# SSTuino_Evo.net
KiCad netlist of a schematic drawn in EAGLE
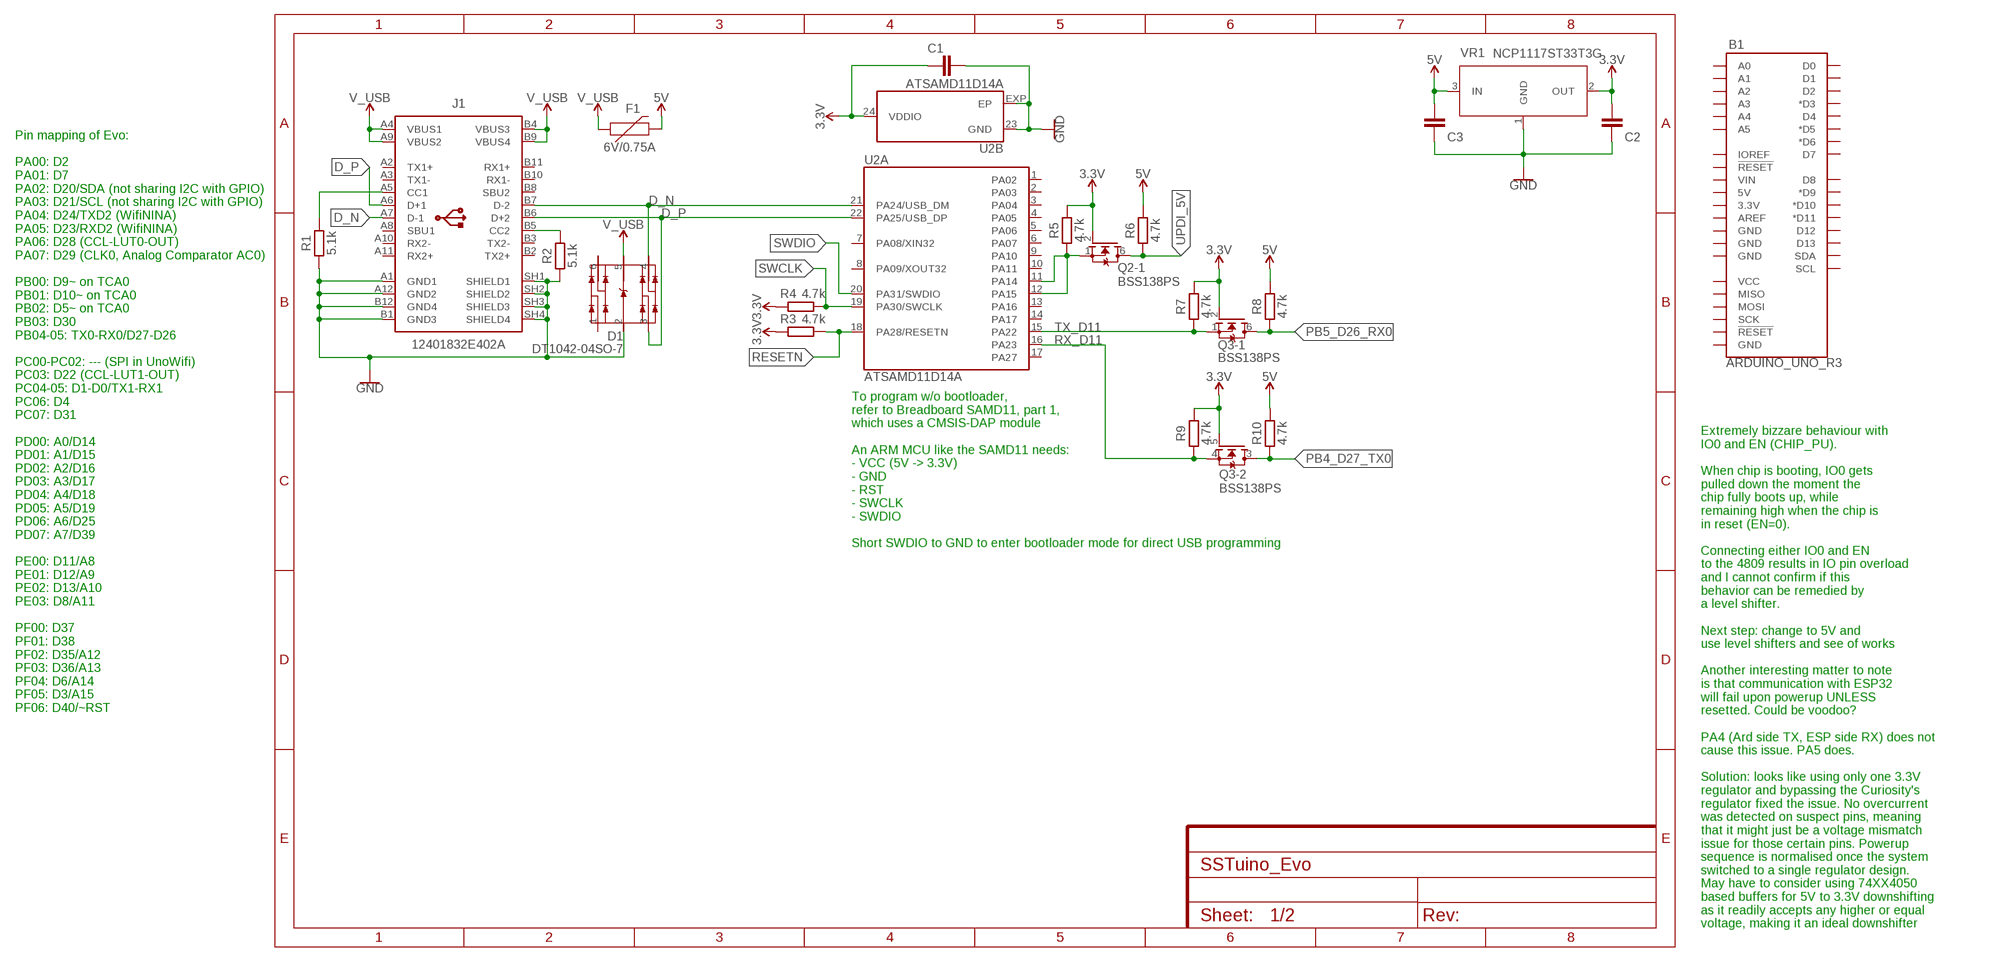
[diagram p0: schematic, sheet 1]
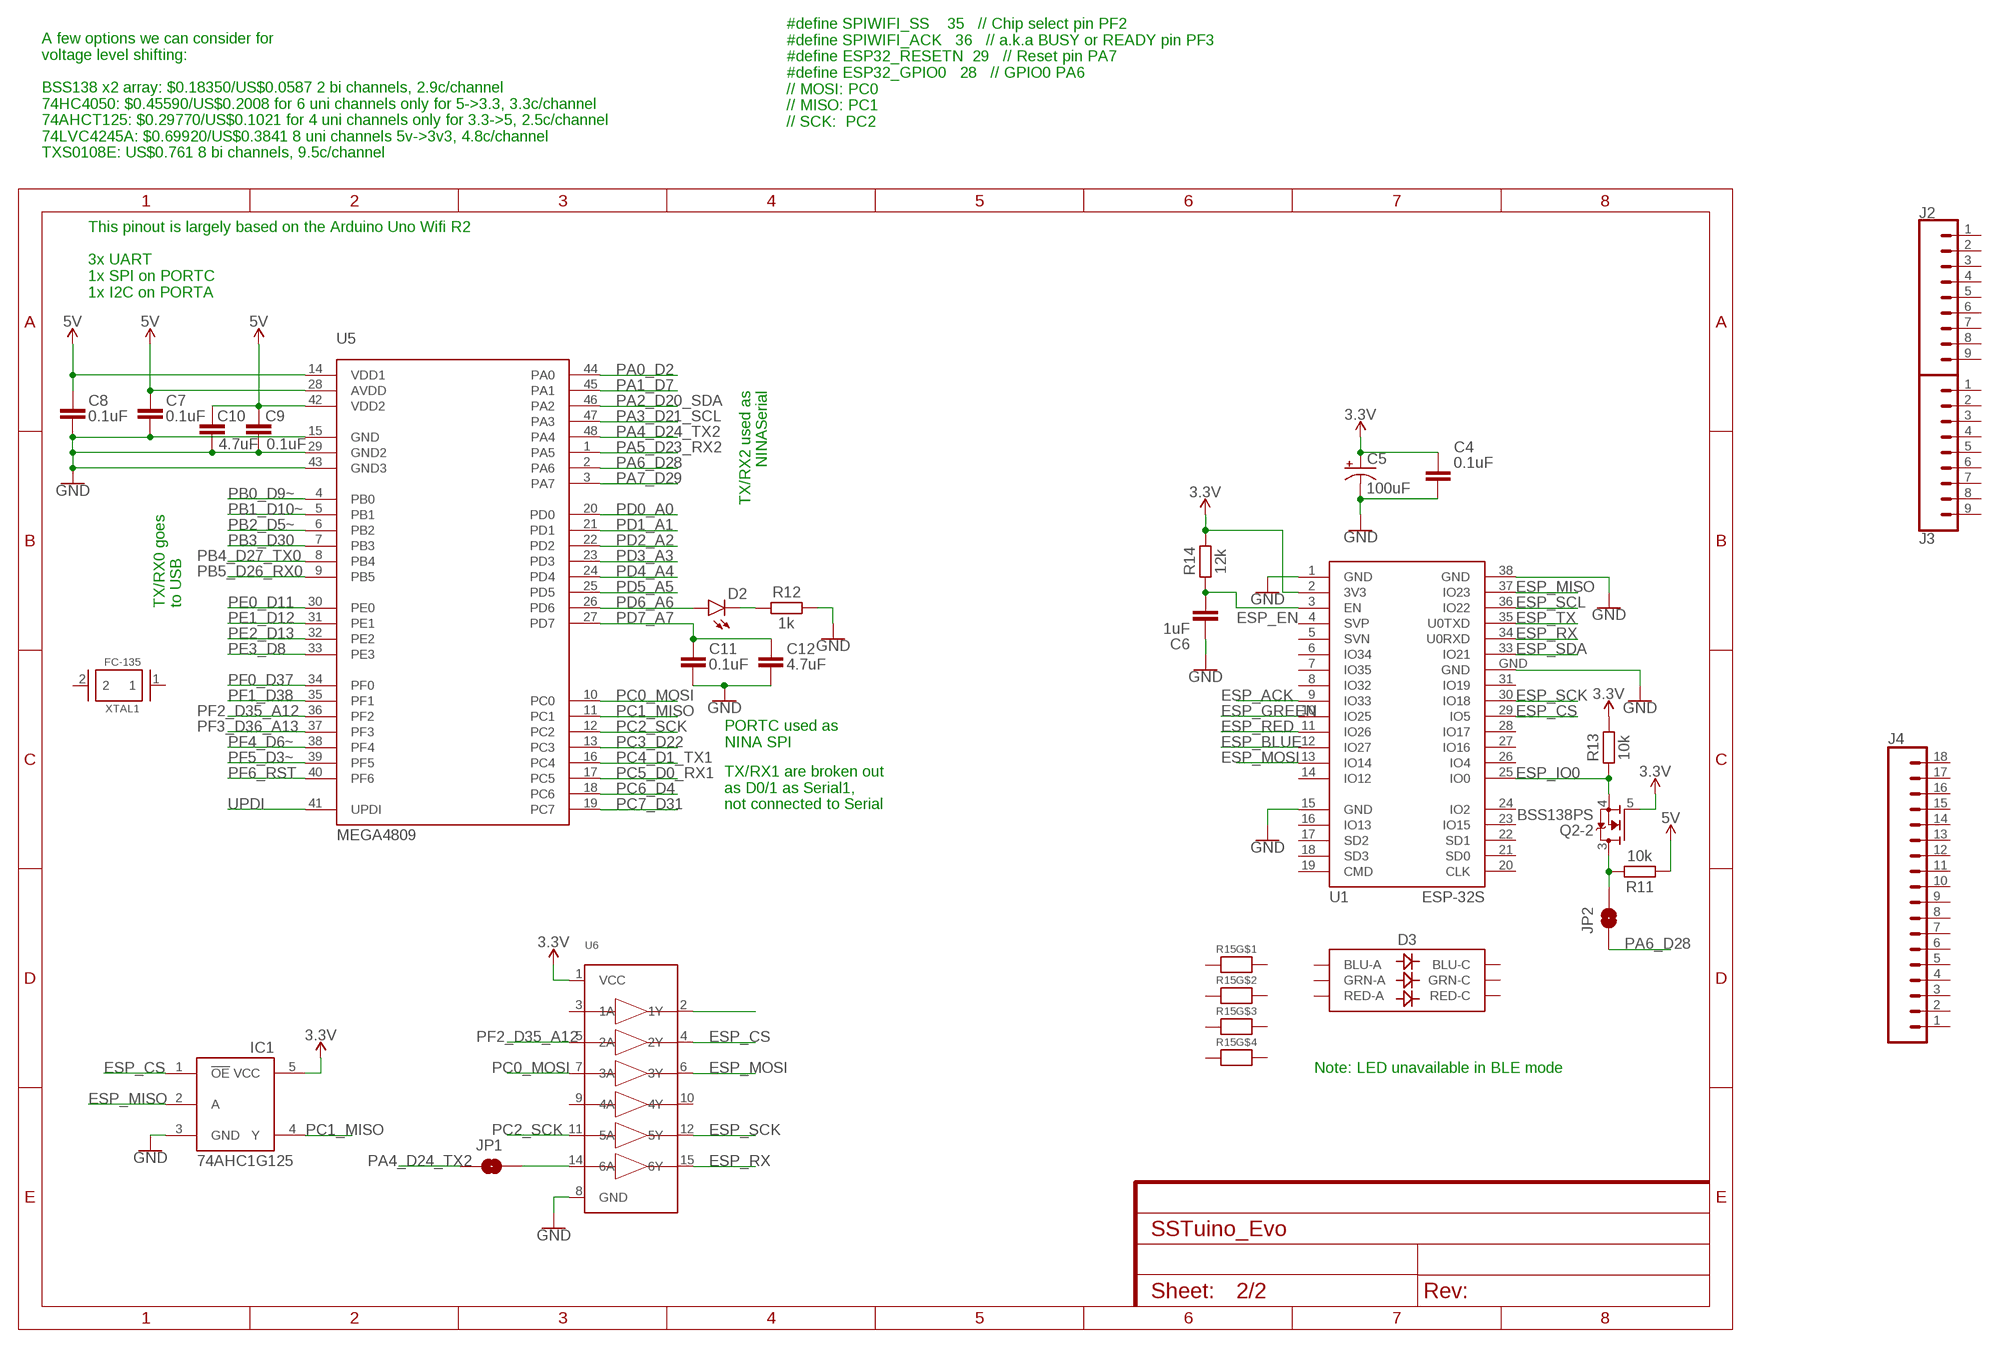
[diagram p1: schematic, sheet 2]

(export (version "E")
  (design (tool "Eeschema 10.0.6"))
  (components
    (comp (ref "C4")
      (value "0.1uF")
      (footprint "eagle-import:CAPC1005X60")
      (libsource (lib "eagle-import") (part "CCHIP-0402(1005-METRIC)_"))
    )
    (comp (ref "C5")
      (value "100uF")
      (footprint "eagle-import:CAPMP3216X180N")
      (libsource (lib "eagle-import") (part "C-POL-USTANTALUM-1206(3216-METRIC)_"))
    )
    (comp (ref "C6")
      (value "1uF")
      (footprint "eagle-import:CAPC1005X60")
      (libsource (lib "eagle-import") (part "CCHIP-0402(1005-METRIC)_"))
    )
    (comp (ref "C7")
      (value "0.1uF")
      (footprint "eagle-import:CAPC1005X60")
      (libsource (lib "eagle-import") (part "CCHIP-0402(1005-METRIC)_"))
    )
    (comp (ref "C8")
      (value "0.1uF")
      (footprint "eagle-import:CAPC1005X60")
      (libsource (lib "eagle-import") (part "CCHIP-0402(1005-METRIC)_"))
    )
    (comp (ref "C9")
      (value "0.1uF")
      (footprint "eagle-import:CAPC1005X60")
      (libsource (lib "eagle-import") (part "CCHIP-0402(1005-METRIC)_"))
    )
    (comp (ref "C10")
      (value "4.7uF")
      (footprint "eagle-import:CAPC1005X60")
      (libsource (lib "eagle-import") (part "CCHIP-0402(1005-METRIC)_"))
    )
    (comp (ref "C11")
      (value "0.1uF")
      (footprint "eagle-import:CAPC1005X60")
      (libsource (lib "eagle-import") (part "CCHIP-0402(1005-METRIC)_"))
    )
    (comp (ref "C12")
      (value "4.7uF")
      (footprint "eagle-import:CAPC1005X60")
      (libsource (lib "eagle-import") (part "CCHIP-0402(1005-METRIC)_"))
    )
    (comp (ref "D2")
      (value "LED0603")
      (footprint "eagle-import:LED-0603")
      (libsource (lib "eagle-import") (part "LED0603"))
    )
    (comp (ref "D3")
      (value "LED-RGBNO_IC")
      (footprint "eagle-import:LED-TRICOLOR-5050")
      (libsource (lib "eagle-import") (part "LED-RGBNO_IC"))
    )
    (comp (ref "IC1")
      (value "74AHC1G125")
      (footprint "eagle-import:SOT23-5L")
      (libsource (lib "eagle-import") (part "74AHC1G125"))
    )
    (comp (ref "J2")
      (value "CONN_09NO_SILK")
      (footprint "eagle-import:1X09_NO_SILK")
      (libsource (lib "eagle-import") (part "CONN_09NO_SILK"))
    )
    (comp (ref "J3")
      (value "CONN_09NO_SILK")
      (footprint "eagle-import:1X09_NO_SILK")
      (libsource (lib "eagle-import") (part "CONN_09NO_SILK"))
    )
    (comp (ref "J4")
      (value "CONN_18")
      (footprint "eagle-import:1X18")
      (libsource (lib "eagle-import") (part "CONN_18"))
    )
    (comp (ref "JP1")
      (value "JUMPER-SMT_2_NO_SILK")
      (footprint "eagle-import:SMT-JUMPER_2_NO_SILK")
      (libsource (lib "eagle-import") (part "JUMPER-SMT_2_NO_SILK"))
    )
    (comp (ref "JP2")
      (value "JUMPER-SMT_2_NO_SILK")
      (footprint "eagle-import:SMT-JUMPER_2_NO_SILK")
      (libsource (lib "eagle-import") (part "JUMPER-SMT_2_NO_SILK"))
    )
    (comp (ref "Q2")
      (value "BSS138PS")
      (footprint "eagle-import:ARDUINO-TRANSISTORS_SOT363")
      (fields (field (name "MANUFACTURER") "NXP"))
      (libsource (lib "eagle-import") (part "BSS138PS"))
    )
    (comp (ref "R11")
      (value "10k")
      (footprint "eagle-import:RESC1005X40")
      (libsource (lib "eagle-import") (part "RCHIP-0402(1005-METRIC)_"))
    )
    (comp (ref "R12")
      (value "1k")
      (footprint "eagle-import:RESC1005X40")
      (libsource (lib "eagle-import") (part "RCHIP-0402(1005-METRIC)_"))
    )
    (comp (ref "R13")
      (value "10k")
      (footprint "eagle-import:RESC1005X40")
      (libsource (lib "eagle-import") (part "RCHIP-0402(1005-METRIC)_"))
    )
    (comp (ref "R14")
      (value "12k")
      (footprint "eagle-import:RESC1005X40")
      (libsource (lib "eagle-import") (part "RCHIP-0402(1005-METRIC)_"))
    )
    (comp (ref "R15")
      (value "RESISTOR_4PACK")
      (footprint "eagle-import:RESPACK_4X0603")
      (libsource (lib "eagle-import") (part "RESISTOR_4PACK"))
    )
    (comp (ref "U1")
      (value "ESP-32S")
      (footprint "eagle-import:ESP-32S")
      (libsource (lib "eagle-import") (part "ESP-32S"))
    )
    (comp (ref "U5")
      (value "MEGA4809")
      (footprint "eagle-import:TQFP48")
      (libsource (lib "eagle-import") (part "MEGA4809"))
    )
    (comp (ref "U6")
      (value "74HC4050DTSSOP")
      (footprint "eagle-import:TSSOP16")
      (libsource (lib "eagle-import") (part "74HC4050DTSSOP"))
    )
    (comp (ref "XTAL1")
      (value "FC-135")
      (footprint "eagle-import:XTAL330X1051X90N")
      (fields (field (name "MANUFACTURER") "Seiko Epson Corporation"))
      (libsource (lib "eagle-import") (part "FC-135"))
    )
    (comp (ref "B1")
      (value "ARDUINO_UNO_R3")
      (footprint "eagle-import:ARDUINO_R3")
      (libsource (lib "eagle-import") (part "ARDUINO_UNO_R3"))
    )
    (comp (ref "C1")
      (value "100n")
      (footprint "eagle-import:CAPC1005X60")
      (libsource (lib "eagle-import") (part "CCHIP-0402(1005-METRIC)_"))
    )
    (comp (ref "C2")
      (value "10uF")
      (footprint "eagle-import:CAPC1608X85")
      (libsource (lib "eagle-import") (part "CCHIP-0603(1608-METRIC)_"))
    )
    (comp (ref "C3")
      (value "10uF")
      (footprint "eagle-import:CAPC1608X85")
      (libsource (lib "eagle-import") (part "CCHIP-0603(1608-METRIC)_"))
    )
    (comp (ref "D1")
      (value "DT1042-04SO-7")
      (footprint "eagle-import:SOT95P285X140-6N")
      (fields (field (name "DIGI-KEY_PART_NUMBER") "DT1042-04SO-7DICT-ND") (field (name "MF") "Diodes Inc."))
      (libsource (lib "eagle-import") (part "DT1042-04SO-7"))
    )
    (comp (ref "F1")
      (value "6V/0.75A")
      (footprint "eagle-import:1206")
      (libsource (lib "eagle-import") (part "PPTC_THREE-QUARTER-AMP"))
    )
    (comp (ref "J1")
      (value "12401832E402A")
      (footprint "eagle-import:12401832E402A")
      (fields (field (name "MANUFACTURER") "Amphenol ICC"))
      (libsource (lib "eagle-import") (part "12401832E402A"))
    )
    (comp (ref "Q3")
      (value "BSS138PS")
      (footprint "eagle-import:ARDUINO-TRANSISTORS_SOT363")
      (fields (field (name "MANUFACTURER") "NXP"))
      (libsource (lib "eagle-import") (part "BSS138PS"))
    )
    (comp (ref "R1")
      (value "5.1k")
      (footprint "eagle-import:RESC1005X40")
      (libsource (lib "eagle-import") (part "RCHIP-0402(1005-METRIC)_"))
    )
    (comp (ref "R2")
      (value "5.1k")
      (footprint "eagle-import:RESC1005X40")
      (libsource (lib "eagle-import") (part "RCHIP-0402(1005-METRIC)_"))
    )
    (comp (ref "R3")
      (value "4.7k")
      (footprint "eagle-import:RESC1005X40")
      (libsource (lib "eagle-import") (part "RCHIP-0402(1005-METRIC)_"))
    )
    (comp (ref "R4")
      (value "4.7k")
      (footprint "eagle-import:RESC1005X40")
      (libsource (lib "eagle-import") (part "RCHIP-0402(1005-METRIC)_"))
    )
    (comp (ref "R5")
      (value "4.7k")
      (footprint "eagle-import:RESC1005X40")
      (libsource (lib "eagle-import") (part "RCHIP-0402(1005-METRIC)_"))
    )
    (comp (ref "R6")
      (value "4.7k")
      (footprint "eagle-import:RESC1005X40")
      (libsource (lib "eagle-import") (part "RCHIP-0402(1005-METRIC)_"))
    )
    (comp (ref "R7")
      (value "4.7k")
      (footprint "eagle-import:RESC1005X40")
      (libsource (lib "eagle-import") (part "RCHIP-0402(1005-METRIC)_"))
    )
    (comp (ref "R8")
      (value "4.7k")
      (footprint "eagle-import:RESC1005X40")
      (libsource (lib "eagle-import") (part "RCHIP-0402(1005-METRIC)_"))
    )
    (comp (ref "R9")
      (value "4.7k")
      (footprint "eagle-import:RESC1005X40")
      (libsource (lib "eagle-import") (part "RCHIP-0402(1005-METRIC)_"))
    )
    (comp (ref "R10")
      (value "4.7k")
      (footprint "eagle-import:RESC1005X40")
      (libsource (lib "eagle-import") (part "RCHIP-0402(1005-METRIC)_"))
    )
    (comp (ref "U2")
      (value "ATSAMD11D14A")
      (footprint "eagle-import:ARDUINO-UCS&SOCS_HVQFN24")
      (fields (field (name "MANUFACTURER") "Microchip"))
      (libsource (lib "eagle-import") (part "ATSAMD11D14"))
    )
    (comp (ref "VR1")
      (value "NCP1117ST33T3G")
      (footprint "eagle-import:SOT230P700X170-4")
      (fields (field (name "MANUFACTURER") "ON Semiconductor"))
      (libsource (lib "eagle-import") (part "NCP1117ST33T3GSOT-223"))
    )
  )
  (nets
    (net (code "1") (name "3.3V") (class "Default")
      (node (ref "C1") (pin "1") (pinfunction "1_1") (pintype "passive"))
      (node (ref "C2") (pin "1") (pinfunction "1_1") (pintype "passive"))
      (node (ref "C4") (pin "1") (pinfunction "1_1") (pintype "passive"))
      (node (ref "C5") (pin "1") (pinfunction "+_1") (pintype "passive"))
      (node (ref "IC1") (pin "5") (pinfunction "VCC_5") (pintype "power_in"))
      (node (ref "Q2") (pin "2") (pinfunction "G_2") (pintype "passive"))
      (node (ref "Q2") (pin "5") (pinfunction "G_5") (pintype "passive"))
      (node (ref "Q3") (pin "2") (pinfunction "G_2") (pintype "passive"))
      (node (ref "Q3") (pin "5") (pinfunction "G_5") (pintype "passive"))
      (node (ref "R13") (pin "2") (pinfunction "2_2") (pintype "passive"))
      (node (ref "R14") (pin "2") (pinfunction "2_2") (pintype "passive"))
      (node (ref "R3") (pin "2") (pinfunction "2_2") (pintype "passive"))
      (node (ref "R4") (pin "2") (pinfunction "2_2") (pintype "passive"))
      (node (ref "R5") (pin "2") (pinfunction "2_2") (pintype "passive"))
      (node (ref "R7") (pin "2") (pinfunction "2_2") (pintype "passive"))
      (node (ref "R9") (pin "2") (pinfunction "2_2") (pintype "passive"))
      (node (ref "U1") (pin "2") (pinfunction "3V3_2") (pintype "power_in"))
      (node (ref "U2") (pin "24") (pinfunction "VDDIO_24") (pintype "power_in"))
      (node (ref "U6") (pin "1") (pinfunction "VCC_1") (pintype "bidirectional"))
      (node (ref "VR1") (pin "2") (pinfunction "OUT_2") (pintype "output"))
    )
    (net (code "2") (name "5V") (class "Default")
      (node (ref "C10") (pin "1") (pinfunction "1_1") (pintype "passive"))
      (node (ref "C3") (pin "1") (pinfunction "1_1") (pintype "passive"))
      (node (ref "C7") (pin "1") (pinfunction "1_1") (pintype "passive"))
      (node (ref "C8") (pin "1") (pinfunction "1_1") (pintype "passive"))
      (node (ref "C9") (pin "1") (pinfunction "1_1") (pintype "passive"))
      (node (ref "F1") (pin "2") (pinfunction "2_2") (pintype "bidirectional"))
      (node (ref "R10") (pin "2") (pinfunction "2_2") (pintype "passive"))
      (node (ref "R11") (pin "1") (pinfunction "1_1") (pintype "passive"))
      (node (ref "R6") (pin "2") (pinfunction "2_2") (pintype "passive"))
      (node (ref "R8") (pin "2") (pinfunction "2_2") (pintype "passive"))
      (node (ref "U5") (pin "14") (pinfunction "VDD1_14") (pintype "bidirectional"))
      (node (ref "U5") (pin "28") (pinfunction "AVDD_28") (pintype "bidirectional"))
      (node (ref "U5") (pin "42") (pinfunction "VDD2_42") (pintype "bidirectional"))
      (node (ref "VR1") (pin "3") (pinfunction "IN_3") (pintype "input"))
    )
    (net (code "3") (name "D_N") (class "Default")
      (node (ref "D1") (pin "4") (pinfunction "IO3_4") (pintype "passive"))
      (node (ref "J1") (pin "A7") (pinfunction "D-1_A7") (pintype "bidirectional"))
      (node (ref "J1") (pin "B7") (pinfunction "D-2_B7") (pintype "bidirectional"))
      (node (ref "U2") (pin "21") (pinfunction "PA24/USB_DM_21") (pintype "bidirectional"))
    )
    (net (code "4") (name "D_P") (class "Default")
      (node (ref "D1") (pin "3") (pinfunction "IO2_3") (pintype "passive"))
      (node (ref "J1") (pin "A6") (pinfunction "D+1_A6") (pintype "bidirectional"))
      (node (ref "J1") (pin "B6") (pinfunction "D+2_B6") (pintype "bidirectional"))
      (node (ref "U2") (pin "22") (pinfunction "PA25/USB_DP_22") (pintype "bidirectional"))
    )
    (net (code "5") (name "ESP_ACK") (class "Default")
      (node (ref "U1") (pin "9") (pinfunction "IO33_9") (pintype "bidirectional"))
    )
    (net (code "6") (name "ESP_BLUE") (class "Default")
      (node (ref "U1") (pin "12") (pinfunction "IO27_12") (pintype "bidirectional"))
    )
    (net (code "7") (name "ESP_CS") (class "Default")
      (node (ref "IC1") (pin "1") (pinfunction "~{OE}_1") (pintype "input"))
      (node (ref "U1") (pin "29") (pinfunction "IO5_29") (pintype "bidirectional"))
      (node (ref "U6") (pin "4") (pinfunction "2Y_4") (pintype "bidirectional"))
    )
    (net (code "8") (name "ESP_EN") (class "Default")
      (node (ref "C6") (pin "2") (pinfunction "2_2") (pintype "passive"))
      (node (ref "R14") (pin "1") (pinfunction "1_1") (pintype "passive"))
      (node (ref "U1") (pin "3") (pinfunction "EN_3") (pintype "input"))
    )
    (net (code "9") (name "ESP_GREEN") (class "Default")
      (node (ref "U1") (pin "10") (pinfunction "IO25_10") (pintype "bidirectional"))
    )
    (net (code "10") (name "ESP_IO0") (class "Default")
      (node (ref "Q2") (pin "4") (pinfunction "S_4") (pintype "passive"))
      (node (ref "R13") (pin "1") (pinfunction "1_1") (pintype "passive"))
      (node (ref "U1") (pin "25") (pinfunction "IO0_25") (pintype "bidirectional"))
    )
    (net (code "11") (name "ESP_MISO") (class "Default")
      (node (ref "IC1") (pin "2") (pinfunction "A_2") (pintype "input"))
      (node (ref "U1") (pin "37") (pinfunction "IO23_37") (pintype "bidirectional"))
    )
    (net (code "12") (name "ESP_MOSI") (class "Default")
      (node (ref "U1") (pin "13") (pinfunction "IO14_13") (pintype "bidirectional"))
      (node (ref "U6") (pin "6") (pinfunction "3Y_6") (pintype "bidirectional"))
    )
    (net (code "13") (name "ESP_RED") (class "Default")
      (node (ref "U1") (pin "11") (pinfunction "IO26_11") (pintype "bidirectional"))
    )
    (net (code "14") (name "ESP_RX") (class "Default")
      (node (ref "U1") (pin "34") (pinfunction "U0RXD_34") (pintype "bidirectional"))
      (node (ref "U6") (pin "15") (pinfunction "6Y_15") (pintype "bidirectional"))
    )
    (net (code "15") (name "ESP_SCK") (class "Default")
      (node (ref "U1") (pin "30") (pinfunction "IO18_30") (pintype "bidirectional"))
      (node (ref "U6") (pin "12") (pinfunction "5Y_12") (pintype "bidirectional"))
    )
    (net (code "16") (name "ESP_SCL") (class "Default")
      (node (ref "U1") (pin "36") (pinfunction "IO22_36") (pintype "bidirectional"))
    )
    (net (code "17") (name "ESP_SDA") (class "Default")
      (node (ref "U1") (pin "33") (pinfunction "IO21_33") (pintype "bidirectional"))
    )
    (net (code "18") (name "ESP_TX") (class "Default")
      (node (ref "U1") (pin "35") (pinfunction "U0TXD_35") (pintype "bidirectional"))
    )
    (net (code "19") (name "GND") (class "Default")
      (node (ref "C1") (pin "2") (pinfunction "2_2") (pintype "passive"))
      (node (ref "C10") (pin "2") (pinfunction "2_2") (pintype "passive"))
      (node (ref "C11") (pin "2") (pinfunction "2_2") (pintype "passive"))
      (node (ref "C12") (pin "2") (pinfunction "2_2") (pintype "passive"))
      (node (ref "C2") (pin "2") (pinfunction "2_2") (pintype "passive"))
      (node (ref "C3") (pin "2") (pinfunction "2_2") (pintype "passive"))
      (node (ref "C4") (pin "2") (pinfunction "2_2") (pintype "passive"))
      (node (ref "C5") (pin "2") (pinfunction "-_2") (pintype "passive"))
      (node (ref "C6") (pin "1") (pinfunction "1_1") (pintype "passive"))
      (node (ref "C7") (pin "2") (pinfunction "2_2") (pintype "passive"))
      (node (ref "C8") (pin "2") (pinfunction "2_2") (pintype "passive"))
      (node (ref "C9") (pin "2") (pinfunction "2_2") (pintype "passive"))
      (node (ref "D1") (pin "2") (pinfunction "VSS_2") (pintype "power_in"))
      (node (ref "IC1") (pin "3") (pinfunction "GND_3") (pintype "power_in"))
      (node (ref "J1") (pin "A1") (pinfunction "GND1_A1") (pintype "power_in"))
      (node (ref "J1") (pin "A12") (pinfunction "GND2_A12") (pintype "power_in"))
      (node (ref "J1") (pin "B1") (pinfunction "GND3_B1") (pintype "power_in"))
      (node (ref "J1") (pin "B12") (pinfunction "GND4_B12") (pintype "power_in"))
      (node (ref "J1") (pin "SH1") (pinfunction "SHIELD1_SH1") (pintype "power_in"))
      (node (ref "J1") (pin "SH2") (pinfunction "SHIELD2_SH2") (pintype "power_in"))
      (node (ref "J1") (pin "SH3") (pinfunction "SHIELD3_SH3") (pintype "power_in"))
      (node (ref "J1") (pin "SH4") (pinfunction "SHIELD4_SH4") (pintype "power_in"))
      (node (ref "R1") (pin "1") (pinfunction "1_1") (pintype "passive"))
      (node (ref "R12") (pin "2") (pinfunction "2_2") (pintype "passive"))
      (node (ref "R2") (pin "1") (pinfunction "1_1") (pintype "passive"))
      (node (ref "U1") (pin "1") (pinfunction "GND_1") (pintype "power_in"))
      (node (ref "U1") (pin "15") (pinfunction "GND_15") (pintype "power_in"))
      (node (ref "U1") (pin "38") (pinfunction "GND_38") (pintype "power_in"))
      (node (ref "U1") (pin "GND") (pinfunction "GND_GND") (pintype "power_in"))
      (node (ref "U2") (pin "23") (pinfunction "GND_23") (pintype "power_in"))
      (node (ref "U2") (pin "EXP") (pinfunction "EP_EXP") (pintype "power_in"))
      (node (ref "U5") (pin "15") (pinfunction "GND_15") (pintype "bidirectional"))
      (node (ref "U5") (pin "29") (pinfunction "GND2_29") (pintype "bidirectional"))
      (node (ref "U5") (pin "43") (pinfunction "GND3_43") (pintype "bidirectional"))
      (node (ref "U6") (pin "8") (pinfunction "GND_8") (pintype "bidirectional"))
      (node (ref "VR1") (pin "1") (pinfunction "GND_1") (pintype "passive"))
    )
    (net (code "20") (name "Net-(D2-PadC)") (class "Default")
      (node (ref "D2") (pin "C") (pinfunction "C_C") (pintype "passive"))
      (node (ref "R12") (pin "1") (pinfunction "1_1") (pintype "passive"))
    )
    (net (code "21") (name "Net-(J1-CC1)") (class "Default")
      (node (ref "J1") (pin "A5") (pinfunction "CC1_A5") (pintype "bidirectional"))
      (node (ref "R1") (pin "2") (pinfunction "2_2") (pintype "passive"))
    )
    (net (code "22") (name "Net-(J1-CC2)") (class "Default")
      (node (ref "J1") (pin "B5") (pinfunction "CC2_B5") (pintype "bidirectional"))
      (node (ref "R2") (pin "2") (pinfunction "2_2") (pintype "passive"))
    )
    (net (code "23") (name "Net-(Q2A-S)") (class "Default")
      (node (ref "Q2") (pin "1") (pinfunction "S_1") (pintype "passive"))
      (node (ref "R5") (pin "1") (pinfunction "1_1") (pintype "passive"))
      (node (ref "U2") (pin "11") (pinfunction "PA14_11") (pintype "bidirectional"))
      (node (ref "U2") (pin "12") (pinfunction "PA15_12") (pintype "bidirectional"))
    )
    (net (code "24") (name "Net-(Q2B-D)") (class "Default")
      (node (ref "JP2") (pin "2") (pinfunction "2_2") (pintype "passive"))
      (node (ref "Q2") (pin "3") (pinfunction "D_3") (pintype "passive"))
      (node (ref "R11") (pin "2") (pinfunction "2_2") (pintype "passive"))
    )
    (net (code "25") (name "Net-(U6-6A)") (class "Default")
      (node (ref "JP1") (pin "2") (pinfunction "2_2") (pintype "passive"))
      (node (ref "U6") (pin "14") (pinfunction "6A_14") (pintype "bidirectional"))
    )
    (net (code "26") (name "PA0_D2") (class "Default")
      (node (ref "U5") (pin "44") (pinfunction "PA0_44") (pintype "bidirectional"))
    )
    (net (code "27") (name "PA1_D7") (class "Default")
      (node (ref "U5") (pin "45") (pinfunction "PA1_45") (pintype "bidirectional"))
    )
    (net (code "28") (name "PA2_D20_SDA") (class "Default")
      (node (ref "U5") (pin "46") (pinfunction "PA2_46") (pintype "bidirectional"))
    )
    (net (code "29") (name "PA3_D21_SCL") (class "Default")
      (node (ref "U5") (pin "47") (pinfunction "PA3_47") (pintype "bidirectional"))
    )
    (net (code "30") (name "PA4_D24_TX2") (class "Default")
      (node (ref "JP1") (pin "1") (pinfunction "1_1") (pintype "passive"))
      (node (ref "U5") (pin "48") (pinfunction "PA4_48") (pintype "bidirectional"))
    )
    (net (code "31") (name "PA5_D23_RX2") (class "Default")
      (node (ref "U5") (pin "1") (pinfunction "PA5_1") (pintype "bidirectional"))
    )
    (net (code "32") (name "PA6_D28") (class "Default")
      (node (ref "JP2") (pin "1") (pinfunction "1_1") (pintype "passive"))
      (node (ref "U5") (pin "2") (pinfunction "PA6_2") (pintype "bidirectional"))
    )
    (net (code "33") (name "PA7_D29") (class "Default")
      (node (ref "U5") (pin "3") (pinfunction "PA7_3") (pintype "bidirectional"))
    )
    (net (code "34") (name "PB0_D9~{}") (class "Default")
      (node (ref "U5") (pin "4") (pinfunction "PB0_4") (pintype "bidirectional"))
    )
    (net (code "35") (name "PB1_D10~{}") (class "Default")
      (node (ref "U5") (pin "5") (pinfunction "PB1_5") (pintype "bidirectional"))
    )
    (net (code "36") (name "PB2_D5~{}") (class "Default")
      (node (ref "U5") (pin "6") (pinfunction "PB2_6") (pintype "bidirectional"))
    )
    (net (code "37") (name "PB3_D30") (class "Default")
      (node (ref "U5") (pin "7") (pinfunction "PB3_7") (pintype "bidirectional"))
    )
    (net (code "38") (name "PB4_D27_TX0") (class "Default")
      (node (ref "Q3") (pin "3") (pinfunction "D_3") (pintype "passive"))
      (node (ref "R10") (pin "1") (pinfunction "1_1") (pintype "passive"))
      (node (ref "U5") (pin "8") (pinfunction "PB4_8") (pintype "bidirectional"))
    )
    (net (code "39") (name "PB5_D26_RX0") (class "Default")
      (node (ref "Q3") (pin "6") (pinfunction "D_6") (pintype "passive"))
      (node (ref "R8") (pin "1") (pinfunction "1_1") (pintype "passive"))
      (node (ref "U5") (pin "9") (pinfunction "PB5_9") (pintype "bidirectional"))
    )
    (net (code "40") (name "PC0_MOSI") (class "Default")
      (node (ref "U5") (pin "10") (pinfunction "PC0_10") (pintype "bidirectional"))
      (node (ref "U6") (pin "7") (pinfunction "3A_7") (pintype "bidirectional"))
    )
    (net (code "41") (name "PC1_MISO") (class "Default")
      (node (ref "IC1") (pin "4") (pinfunction "Y_4") (pintype "output"))
      (node (ref "U5") (pin "11") (pinfunction "PC1_11") (pintype "bidirectional"))
    )
    (net (code "42") (name "PC2_SCK") (class "Default")
      (node (ref "U5") (pin "12") (pinfunction "PC2_12") (pintype "bidirectional"))
      (node (ref "U6") (pin "11") (pinfunction "5A_11") (pintype "bidirectional"))
    )
    (net (code "43") (name "PC3_D22") (class "Default")
      (node (ref "U5") (pin "13") (pinfunction "PC3_13") (pintype "bidirectional"))
    )
    (net (code "44") (name "PC4_D1_TX1") (class "Default")
      (node (ref "U5") (pin "16") (pinfunction "PC4_16") (pintype "bidirectional"))
    )
    (net (code "45") (name "PC5_D0_RX1") (class "Default")
      (node (ref "U5") (pin "17") (pinfunction "PC5_17") (pintype "bidirectional"))
    )
    (net (code "46") (name "PC6_D4") (class "Default")
      (node (ref "U5") (pin "18") (pinfunction "PC6_18") (pintype "bidirectional"))
    )
    (net (code "47") (name "PC7_D31") (class "Default")
      (node (ref "U5") (pin "19") (pinfunction "PC7_19") (pintype "bidirectional"))
    )
    (net (code "48") (name "PD0_A0") (class "Default")
      (node (ref "U5") (pin "20") (pinfunction "PD0_20") (pintype "bidirectional"))
    )
    (net (code "49") (name "PD1_A1") (class "Default")
      (node (ref "U5") (pin "21") (pinfunction "PD1_21") (pintype "bidirectional"))
    )
    (net (code "50") (name "PD2_A2") (class "Default")
      (node (ref "U5") (pin "22") (pinfunction "PD2_22") (pintype "bidirectional"))
    )
    (net (code "51") (name "PD3_A3") (class "Default")
      (node (ref "U5") (pin "23") (pinfunction "PD3_23") (pintype "bidirectional"))
    )
    (net (code "52") (name "PD4_A4") (class "Default")
      (node (ref "U5") (pin "24") (pinfunction "PD4_24") (pintype "bidirectional"))
    )
    (net (code "53") (name "PD5_A5") (class "Default")
      (node (ref "U5") (pin "25") (pinfunction "PD5_25") (pintype "bidirectional"))
    )
    (net (code "54") (name "PD6_A6") (class "Default")
      (node (ref "D2") (pin "A") (pinfunction "A_A") (pintype "passive"))
      (node (ref "U5") (pin "26") (pinfunction "PD6_26") (pintype "bidirectional"))
    )
    (net (code "55") (name "PD7_A7") (class "Default")
      (node (ref "C11") (pin "1") (pinfunction "1_1") (pintype "passive"))
      (node (ref "C12") (pin "1") (pinfunction "1_1") (pintype "passive"))
      (node (ref "U5") (pin "27") (pinfunction "PD7_27") (pintype "bidirectional"))
    )
    (net (code "56") (name "PE0_D11") (class "Default")
      (node (ref "U5") (pin "30") (pinfunction "PE0_30") (pintype "bidirectional"))
    )
    (net (code "57") (name "PE1_D12") (class "Default")
      (node (ref "U5") (pin "31") (pinfunction "PE1_31") (pintype "bidirectional"))
    )
    (net (code "58") (name "PE2_D13") (class "Default")
      (node (ref "U5") (pin "32") (pinfunction "PE2_32") (pintype "bidirectional"))
    )
    (net (code "59") (name "PE3_D8") (class "Default")
      (node (ref "U5") (pin "33") (pinfunction "PE3_33") (pintype "bidirectional"))
    )
    (net (code "60") (name "PF0_D37") (class "Default")
      (node (ref "U5") (pin "34") (pinfunction "PF0_34") (pintype "bidirectional"))
    )
    (net (code "61") (name "PF1_D38") (class "Default")
      (node (ref "U5") (pin "35") (pinfunction "PF1_35") (pintype "bidirectional"))
    )
    (net (code "62") (name "PF2_D35_A12") (class "Default")
      (node (ref "U5") (pin "36") (pinfunction "PF2_36") (pintype "bidirectional"))
      (node (ref "U6") (pin "5") (pinfunction "2A_5") (pintype "bidirectional"))
    )
    (net (code "63") (name "PF3_D36_A13") (class "Default")
      (node (ref "U5") (pin "37") (pinfunction "PF3_37") (pintype "bidirectional"))
    )
    (net (code "64") (name "PF4_D6~{}") (class "Default")
      (node (ref "U5") (pin "38") (pinfunction "PF4_38") (pintype "bidirectional"))
    )
    (net (code "65") (name "PF5_D3~{}") (class "Default")
      (node (ref "U5") (pin "39") (pinfunction "PF5_39") (pintype "bidirectional"))
    )
    (net (code "66") (name "PF6_RST") (class "Default")
      (node (ref "U5") (pin "40") (pinfunction "PF6_40") (pintype "bidirectional"))
    )
    (net (code "67") (name "RESETN") (class "Default")
      (node (ref "R3") (pin "1") (pinfunction "1_1") (pintype "passive"))
      (node (ref "U2") (pin "18") (pinfunction "PA28/RESETN_18") (pintype "bidirectional"))
    )
    (net (code "68") (name "RX_D11") (class "Default")
      (node (ref "Q3") (pin "4") (pinfunction "S_4") (pintype "passive"))
      (node (ref "R9") (pin "1") (pinfunction "1_1") (pintype "passive"))
      (node (ref "U2") (pin "16") (pinfunction "PA23_16") (pintype "bidirectional"))
    )
    (net (code "69") (name "SWCLK") (class "Default")
      (node (ref "R4") (pin "1") (pinfunction "1_1") (pintype "passive"))
      (node (ref "U2") (pin "19") (pinfunction "PA30/SWCLK_19") (pintype "bidirectional"))
    )
    (net (code "70") (name "SWDIO") (class "Default")
      (node (ref "U2") (pin "20") (pinfunction "PA31/SWDIO_20") (pintype "bidirectional"))
    )
    (net (code "71") (name "TX_D11") (class "Default")
      (node (ref "Q3") (pin "1") (pinfunction "S_1") (pintype "passive"))
      (node (ref "R7") (pin "1") (pinfunction "1_1") (pintype "passive"))
      (node (ref "U2") (pin "15") (pinfunction "PA22_15") (pintype "bidirectional"))
    )
    (net (code "72") (name "UPDI") (class "Default")
      (node (ref "U5") (pin "41") (pinfunction "UPDI_41") (pintype "bidirectional"))
    )
    (net (code "73") (name "UPDI_5V") (class "Default")
      (node (ref "Q2") (pin "6") (pinfunction "D_6") (pintype "passive"))
      (node (ref "R6") (pin "1") (pinfunction "1_1") (pintype "passive"))
    )
    (net (code "74") (name "V_USB") (class "Default")
      (node (ref "D1") (pin "5") (pinfunction "VCC_5") (pintype "power_in"))
      (node (ref "F1") (pin "1") (pinfunction "1_1") (pintype "bidirectional"))
      (node (ref "J1") (pin "A4") (pinfunction "VBUS1_A4") (pintype "power_in"))
      (node (ref "J1") (pin "A9") (pinfunction "VBUS2_A9") (pintype "power_in"))
      (node (ref "J1") (pin "B4") (pinfunction "VBUS3_B4") (pintype "power_in"))
      (node (ref "J1") (pin "B9") (pinfunction "VBUS4_B9") (pintype "power_in"))
    )
    (net (code "75") (name "unconnected-(B1-*D3-PadD3)") (class "Default")
      (node (ref "B1") (pin "D3") (pinfunction "*D3_D3") (pintype "bidirectional"))
    )
    (net (code "76") (name "unconnected-(B1-*D5-PadD5)") (class "Default")
      (node (ref "B1") (pin "D5") (pinfunction "*D5_D5") (pintype "bidirectional"))
    )
    (net (code "77") (name "unconnected-(B1-*D6-PadD6)") (class "Default")
      (node (ref "B1") (pin "D6") (pinfunction "*D6_D6") (pintype "bidirectional"))
    )
    (net (code "78") (name "unconnected-(B1-*D9-PadD9)") (class "Default")
      (node (ref "B1") (pin "D9") (pinfunction "*D9_D9") (pintype "bidirectional"))
    )
    (net (code "79") (name "unconnected-(B1-*D10-PadD10)") (class "Default")
      (node (ref "B1") (pin "D10") (pinfunction "*D10_D10") (pintype "bidirectional"))
    )
    (net (code "80") (name "unconnected-(B1-*D11-PadD11)") (class "Default")
      (node (ref "B1") (pin "D11") (pinfunction "*D11_D11") (pintype "bidirectional"))
    )
    (net (code "81") (name "unconnected-(B1-GND-PadGND@1)") (class "Default")
      (node (ref "B1") (pin "GND@1") (pinfunction "GND_GND@1") (pintype "bidirectional"))
    )
    (net (code "82") (name "unconnected-(B1-GND-PadGND@2)") (class "Default")
      (node (ref "B1") (pin "GND@2") (pinfunction "GND_GND@2") (pintype "bidirectional"))
    )
    (net (code "83") (name "unconnected-(B1-GND-PadGND@3)") (class "Default")
      (node (ref "B1") (pin "GND@3") (pinfunction "GND_GND@3") (pintype "bidirectional"))
    )
    (net (code "84") (name "unconnected-(B1-GND-PadGND@4)") (class "Default")
      (node (ref "B1") (pin "GND@4") (pinfunction "GND_GND@4") (pintype "bidirectional"))
    )
    (net (code "85") (name "unconnected-(B1-Pad3.3V)") (class "Default")
      (node (ref "B1") (pin "3.3V") (pinfunction "3.3V_3.3V") (pintype "bidirectional"))
    )
    (net (code "86") (name "unconnected-(B1-Pad5V)") (class "Default")
      (node (ref "B1") (pin "5V") (pinfunction "5V_5V") (pintype "bidirectional"))
    )
    (net (code "87") (name "unconnected-(B1-PadA0)") (class "Default")
      (node (ref "B1") (pin "A0") (pinfunction "A0_A0") (pintype "bidirectional"))
    )
    (net (code "88") (name "unconnected-(B1-PadA1)") (class "Default")
      (node (ref "B1") (pin "A1") (pinfunction "A1_A1") (pintype "bidirectional"))
    )
    (net (code "89") (name "unconnected-(B1-PadA2)") (class "Default")
      (node (ref "B1") (pin "A2") (pinfunction "A2_A2") (pintype "bidirectional"))
    )
    (net (code "90") (name "unconnected-(B1-PadA3)") (class "Default")
      (node (ref "B1") (pin "A3") (pinfunction "A3_A3") (pintype "bidirectional"))
    )
    (net (code "91") (name "unconnected-(B1-PadA4)") (class "Default")
      (node (ref "B1") (pin "A4") (pinfunction "A4_A4") (pintype "bidirectional"))
    )
    (net (code "92") (name "unconnected-(B1-PadA5)") (class "Default")
      (node (ref "B1") (pin "A5") (pinfunction "A5_A5") (pintype "bidirectional"))
    )
    (net (code "93") (name "unconnected-(B1-PadAREF)") (class "Default")
      (node (ref "B1") (pin "AREF") (pinfunction "AREF_AREF") (pintype "bidirectional"))
    )
    (net (code "94") (name "unconnected-(B1-PadD0)") (class "Default")
      (node (ref "B1") (pin "D0") (pinfunction "D0_D0") (pintype "bidirectional"))
    )
    (net (code "95") (name "unconnected-(B1-PadD1)") (class "Default")
      (node (ref "B1") (pin "D1") (pinfunction "D1_D1") (pintype "bidirectional"))
    )
    (net (code "96") (name "unconnected-(B1-PadD2)") (class "Default")
      (node (ref "B1") (pin "D2") (pinfunction "D2_D2") (pintype "bidirectional"))
    )
    (net (code "97") (name "unconnected-(B1-PadD4)") (class "Default")
      (node (ref "B1") (pin "D4") (pinfunction "D4_D4") (pintype "bidirectional"))
    )
    (net (code "98") (name "unconnected-(B1-PadD7)") (class "Default")
      (node (ref "B1") (pin "D7") (pinfunction "D7_D7") (pintype "bidirectional"))
    )
    (net (code "99") (name "unconnected-(B1-PadD8)") (class "Default")
      (node (ref "B1") (pin "D8") (pinfunction "D8_D8") (pintype "bidirectional"))
    )
    (net (code "100") (name "unconnected-(B1-PadD12)") (class "Default")
      (node (ref "B1") (pin "D12") (pinfunction "D12_D12") (pintype "bidirectional"))
    )
    (net (code "101") (name "unconnected-(B1-PadD13)") (class "Default")
      (node (ref "B1") (pin "D13") (pinfunction "D13_D13") (pintype "bidirectional"))
    )
    (net (code "102") (name "unconnected-(B1-PadIOREF)") (class "Default")
      (node (ref "B1") (pin "IOREF") (pinfunction "IOREF_IOREF") (pintype "bidirectional"))
    )
    (net (code "103") (name "unconnected-(B1-PadMISO)") (class "Default")
      (node (ref "B1") (pin "MISO") (pinfunction "MISO_MISO") (pintype "bidirectional"))
    )
    (net (code "104") (name "unconnected-(B1-PadMOSI)") (class "Default")
      (node (ref "B1") (pin "MOSI") (pinfunction "MOSI_MOSI") (pintype "bidirectional"))
    )
    (net (code "105") (name "unconnected-(B1-PadSCK)") (class "Default")
      (node (ref "B1") (pin "SCK") (pinfunction "SCK_SCK") (pintype "bidirectional"))
    )
    (net (code "106") (name "unconnected-(B1-PadSCL)") (class "Default")
      (node (ref "B1") (pin "SCL") (pinfunction "SCL_SCL") (pintype "bidirectional"))
    )
    (net (code "107") (name "unconnected-(B1-PadSDA)") (class "Default")
      (node (ref "B1") (pin "SDA") (pinfunction "SDA_SDA") (pintype "bidirectional"))
    )
    (net (code "108") (name "unconnected-(B1-PadVCC)") (class "Default")
      (node (ref "B1") (pin "VCC") (pinfunction "VCC_VCC") (pintype "bidirectional"))
    )
    (net (code "109") (name "unconnected-(B1-PadVIN)") (class "Default")
      (node (ref "B1") (pin "VIN") (pinfunction "VIN_VIN") (pintype "bidirectional"))
    )
    (net (code "110") (name "unconnected-(B1-~{RESET}-PadRESET@1)") (class "Default")
      (node (ref "B1") (pin "RESET@1") (pinfunction "~{RESET}_RESET@1") (pintype "bidirectional"))
    )
    (net (code "111") (name "unconnected-(B1-~{RESET}-PadRESET@2)") (class "Default")
      (node (ref "B1") (pin "RESET@2") (pinfunction "~{RESET}_RESET@2") (pintype "bidirectional"))
    )
    (net (code "112") (name "unconnected-(D1-IO1-Pad1)") (class "Default")
      (node (ref "D1") (pin "1") (pinfunction "IO1_1") (pintype "passive"))
    )
    (net (code "113") (name "unconnected-(D1-IO4-Pad6)") (class "Default")
      (node (ref "D1") (pin "6") (pinfunction "IO4_6") (pintype "passive"))
    )
    (net (code "114") (name "unconnected-(D3-BLU-A-Pad3)") (class "Default")
      (node (ref "D3") (pin "3") (pinfunction "BLU-A_3") (pintype "bidirectional"))
    )
    (net (code "115") (name "unconnected-(D3-BLU-C-Pad4)") (class "Default")
      (node (ref "D3") (pin "4") (pinfunction "BLU-C_4") (pintype "bidirectional"))
    )
    (net (code "116") (name "unconnected-(D3-GRN-A-Pad1)") (class "Default")
      (node (ref "D3") (pin "1") (pinfunction "GRN-A_1") (pintype "bidirectional"))
    )
    (net (code "117") (name "unconnected-(D3-GRN-C-Pad6)") (class "Default")
      (node (ref "D3") (pin "6") (pinfunction "GRN-C_6") (pintype "bidirectional"))
    )
    (net (code "118") (name "unconnected-(D3-RED-A-Pad2)") (class "Default")
      (node (ref "D3") (pin "2") (pinfunction "RED-A_2") (pintype "bidirectional"))
    )
    (net (code "119") (name "unconnected-(D3-RED-C-Pad5)") (class "Default")
      (node (ref "D3") (pin "5") (pinfunction "RED-C_5") (pintype "bidirectional"))
    )
    (net (code "120") (name "unconnected-(J1-RX1+-PadB11)") (class "Default")
      (node (ref "J1") (pin "B11") (pinfunction "RX1+_B11") (pintype "bidirectional"))
    )
    (net (code "121") (name "unconnected-(J1-RX1--PadB10)") (class "Default")
      (node (ref "J1") (pin "B10") (pinfunction "RX1-_B10") (pintype "bidirectional"))
    )
    (net (code "122") (name "unconnected-(J1-RX2+-PadA11)") (class "Default")
      (node (ref "J1") (pin "A11") (pinfunction "RX2+_A11") (pintype "bidirectional"))
    )
    (net (code "123") (name "unconnected-(J1-RX2--PadA10)") (class "Default")
      (node (ref "J1") (pin "A10") (pinfunction "RX2-_A10") (pintype "bidirectional"))
    )
    (net (code "124") (name "unconnected-(J1-SBU1-PadA8)") (class "Default")
      (node (ref "J1") (pin "A8") (pinfunction "SBU1_A8") (pintype "bidirectional"))
    )
    (net (code "125") (name "unconnected-(J1-SBU2-PadB8)") (class "Default")
      (node (ref "J1") (pin "B8") (pinfunction "SBU2_B8") (pintype "bidirectional"))
    )
    (net (code "126") (name "unconnected-(J1-TX1+-PadA2)") (class "Default")
      (node (ref "J1") (pin "A2") (pinfunction "TX1+_A2") (pintype "bidirectional"))
    )
    (net (code "127") (name "unconnected-(J1-TX1--PadA3)") (class "Default")
      (node (ref "J1") (pin "A3") (pinfunction "TX1-_A3") (pintype "bidirectional"))
    )
    (net (code "128") (name "unconnected-(J1-TX2+-PadB2)") (class "Default")
      (node (ref "J1") (pin "B2") (pinfunction "TX2+_B2") (pintype "bidirectional"))
    )
    (net (code "129") (name "unconnected-(J1-TX2--PadB3)") (class "Default")
      (node (ref "J1") (pin "B3") (pinfunction "TX2-_B3") (pintype "bidirectional"))
    )
    (net (code "130") (name "unconnected-(J2-Pad1)") (class "Default")
      (node (ref "J2") (pin "1") (pinfunction "1_1") (pintype "passive"))
    )
    (net (code "131") (name "unconnected-(J2-Pad2)") (class "Default")
      (node (ref "J2") (pin "2") (pinfunction "2_2") (pintype "passive"))
    )
    (net (code "132") (name "unconnected-(J2-Pad3)") (class "Default")
      (node (ref "J2") (pin "3") (pinfunction "3_3") (pintype "passive"))
    )
    (net (code "133") (name "unconnected-(J2-Pad4)") (class "Default")
      (node (ref "J2") (pin "4") (pinfunction "4_4") (pintype "passive"))
    )
    (net (code "134") (name "unconnected-(J2-Pad5)") (class "Default")
      (node (ref "J2") (pin "5") (pinfunction "5_5") (pintype "passive"))
    )
    (net (code "135") (name "unconnected-(J2-Pad6)") (class "Default")
      (node (ref "J2") (pin "6") (pinfunction "6_6") (pintype "passive"))
    )
    (net (code "136") (name "unconnected-(J2-Pad7)") (class "Default")
      (node (ref "J2") (pin "7") (pinfunction "7_7") (pintype "passive"))
    )
    (net (code "137") (name "unconnected-(J2-Pad8)") (class "Default")
      (node (ref "J2") (pin "8") (pinfunction "8_8") (pintype "passive"))
    )
    (net (code "138") (name "unconnected-(J2-Pad9)") (class "Default")
      (node (ref "J2") (pin "9") (pinfunction "9_9") (pintype "passive"))
    )
    (net (code "139") (name "unconnected-(J3-Pad1)") (class "Default")
      (node (ref "J3") (pin "1") (pinfunction "1_1") (pintype "passive"))
    )
    (net (code "140") (name "unconnected-(J3-Pad2)") (class "Default")
      (node (ref "J3") (pin "2") (pinfunction "2_2") (pintype "passive"))
    )
    (net (code "141") (name "unconnected-(J3-Pad3)") (class "Default")
      (node (ref "J3") (pin "3") (pinfunction "3_3") (pintype "passive"))
    )
    (net (code "142") (name "unconnected-(J3-Pad4)") (class "Default")
      (node (ref "J3") (pin "4") (pinfunction "4_4") (pintype "passive"))
    )
    (net (code "143") (name "unconnected-(J3-Pad5)") (class "Default")
      (node (ref "J3") (pin "5") (pinfunction "5_5") (pintype "passive"))
    )
    (net (code "144") (name "unconnected-(J3-Pad6)") (class "Default")
      (node (ref "J3") (pin "6") (pinfunction "6_6") (pintype "passive"))
    )
    (net (code "145") (name "unconnected-(J3-Pad7)") (class "Default")
      (node (ref "J3") (pin "7") (pinfunction "7_7") (pintype "passive"))
    )
    (net (code "146") (name "unconnected-(J3-Pad8)") (class "Default")
      (node (ref "J3") (pin "8") (pinfunction "8_8") (pintype "passive"))
    )
    (net (code "147") (name "unconnected-(J3-Pad9)") (class "Default")
      (node (ref "J3") (pin "9") (pinfunction "9_9") (pintype "passive"))
    )
    (net (code "148") (name "unconnected-(J4-Pad1)") (class "Default")
      (node (ref "J4") (pin "1") (pinfunction "1_1") (pintype "passive"))
    )
    (net (code "149") (name "unconnected-(J4-Pad2)") (class "Default")
      (node (ref "J4") (pin "2") (pinfunction "2_2") (pintype "passive"))
    )
    (net (code "150") (name "unconnected-(J4-Pad3)") (class "Default")
      (node (ref "J4") (pin "3") (pinfunction "3_3") (pintype "passive"))
    )
    (net (code "151") (name "unconnected-(J4-Pad4)") (class "Default")
      (node (ref "J4") (pin "4") (pinfunction "4_4") (pintype "passive"))
    )
    (net (code "152") (name "unconnected-(J4-Pad5)") (class "Default")
      (node (ref "J4") (pin "5") (pinfunction "5_5") (pintype "passive"))
    )
    (net (code "153") (name "unconnected-(J4-Pad6)") (class "Default")
      (node (ref "J4") (pin "6") (pinfunction "6_6") (pintype "passive"))
    )
    (net (code "154") (name "unconnected-(J4-Pad7)") (class "Default")
      (node (ref "J4") (pin "7") (pinfunction "7_7") (pintype "passive"))
    )
    (net (code "155") (name "unconnected-(J4-Pad8)") (class "Default")
      (node (ref "J4") (pin "8") (pinfunction "8_8") (pintype "passive"))
    )
    (net (code "156") (name "unconnected-(J4-Pad9)") (class "Default")
      (node (ref "J4") (pin "9") (pinfunction "9_9") (pintype "passive"))
    )
    (net (code "157") (name "unconnected-(J4-Pad10)") (class "Default")
      (node (ref "J4") (pin "10") (pinfunction "10_10") (pintype "passive"))
    )
    (net (code "158") (name "unconnected-(J4-Pad11)") (class "Default")
      (node (ref "J4") (pin "11") (pinfunction "11_11") (pintype "passive"))
    )
    (net (code "159") (name "unconnected-(J4-Pad12)") (class "Default")
      (node (ref "J4") (pin "12") (pinfunction "12_12") (pintype "passive"))
    )
    (net (code "160") (name "unconnected-(J4-Pad13)") (class "Default")
      (node (ref "J4") (pin "13") (pinfunction "13_13") (pintype "passive"))
    )
    (net (code "161") (name "unconnected-(J4-Pad14)") (class "Default")
      (node (ref "J4") (pin "14") (pinfunction "14_14") (pintype "passive"))
    )
    (net (code "162") (name "unconnected-(J4-Pad15)") (class "Default")
      (node (ref "J4") (pin "15") (pinfunction "15_15") (pintype "passive"))
    )
    (net (code "163") (name "unconnected-(J4-Pad16)") (class "Default")
      (node (ref "J4") (pin "16") (pinfunction "16_16") (pintype "passive"))
    )
    (net (code "164") (name "unconnected-(J4-Pad17)") (class "Default")
      (node (ref "J4") (pin "17") (pinfunction "17_17") (pintype "passive"))
    )
    (net (code "165") (name "unconnected-(J4-Pad18)") (class "Default")
      (node (ref "J4") (pin "18") (pinfunction "18_18") (pintype "passive"))
    )
    (net (code "166") (name "unconnected-(R15-Pad1)") (class "Default")
      (node (ref "R15") (pin "1") (pinfunction "1_1") (pintype "passive"))
    )
    (net (code "167") (name "unconnected-(R15A-2-Pad8)") (class "Default")
      (node (ref "R15") (pin "8") (pinfunction "2_8") (pintype "passive"))
    )
    (net (code "168") (name "unconnected-(R15B-1-Pad2)") (class "Default")
      (node (ref "R15") (pin "2") (pinfunction "1_2") (pintype "passive"))
    )
    (net (code "169") (name "unconnected-(R15B-2-Pad7)") (class "Default")
      (node (ref "R15") (pin "7") (pinfunction "2_7") (pintype "passive"))
    )
    (net (code "170") (name "unconnected-(R15C-1-Pad3)") (class "Default")
      (node (ref "R15") (pin "3") (pinfunction "1_3") (pintype "passive"))
    )
    (net (code "171") (name "unconnected-(R15C-2-Pad6)") (class "Default")
      (node (ref "R15") (pin "6") (pinfunction "2_6") (pintype "passive"))
    )
    (net (code "172") (name "unconnected-(R15D-1-Pad4)") (class "Default")
      (node (ref "R15") (pin "4") (pinfunction "1_4") (pintype "passive"))
    )
    (net (code "173") (name "unconnected-(R15D-2-Pad5)") (class "Default")
      (node (ref "R15") (pin "5") (pinfunction "2_5") (pintype "passive"))
    )
    (net (code "174") (name "unconnected-(U1-CLK-Pad20)") (class "Default")
      (node (ref "U1") (pin "20") (pinfunction "CLK_20") (pintype "bidirectional"))
    )
    (net (code "175") (name "unconnected-(U1-CMD-Pad19)") (class "Default")
      (node (ref "U1") (pin "19") (pinfunction "CMD_19") (pintype "bidirectional"))
    )
    (net (code "176") (name "unconnected-(U1-IO2-Pad24)") (class "Default")
      (node (ref "U1") (pin "24") (pinfunction "IO2_24") (pintype "bidirectional"))
    )
    (net (code "177") (name "unconnected-(U1-IO4-Pad26)") (class "Default")
      (node (ref "U1") (pin "26") (pinfunction "IO4_26") (pintype "bidirectional"))
    )
    (net (code "178") (name "unconnected-(U1-IO12-Pad14)") (class "Default")
      (node (ref "U1") (pin "14") (pinfunction "IO12_14") (pintype "bidirectional"))
    )
    (net (code "179") (name "unconnected-(U1-IO13-Pad16)") (class "Default")
      (node (ref "U1") (pin "16") (pinfunction "IO13_16") (pintype "bidirectional"))
    )
    (net (code "180") (name "unconnected-(U1-IO15-Pad23)") (class "Default")
      (node (ref "U1") (pin "23") (pinfunction "IO15_23") (pintype "bidirectional"))
    )
    (net (code "181") (name "unconnected-(U1-IO16-Pad27)") (class "Default")
      (node (ref "U1") (pin "27") (pinfunction "IO16_27") (pintype "bidirectional"))
    )
    (net (code "182") (name "unconnected-(U1-IO17-Pad28)") (class "Default")
      (node (ref "U1") (pin "28") (pinfunction "IO17_28") (pintype "bidirectional"))
    )
    (net (code "183") (name "unconnected-(U1-IO19-Pad31)") (class "Default")
      (node (ref "U1") (pin "31") (pinfunction "IO19_31") (pintype "bidirectional"))
    )
    (net (code "184") (name "unconnected-(U1-IO32-Pad8)") (class "Default")
      (node (ref "U1") (pin "8") (pinfunction "IO32_8") (pintype "bidirectional"))
    )
    (net (code "185") (name "unconnected-(U1-IO34-Pad6)") (class "Default")
      (node (ref "U1") (pin "6") (pinfunction "IO34_6") (pintype "bidirectional"))
    )
    (net (code "186") (name "unconnected-(U1-IO35-Pad7)") (class "Default")
      (node (ref "U1") (pin "7") (pinfunction "IO35_7") (pintype "bidirectional"))
    )
    (net (code "187") (name "unconnected-(U1-SD0-Pad21)") (class "Default")
      (node (ref "U1") (pin "21") (pinfunction "SD0_21") (pintype "bidirectional"))
    )
    (net (code "188") (name "unconnected-(U1-SD1-Pad22)") (class "Default")
      (node (ref "U1") (pin "22") (pinfunction "SD1_22") (pintype "bidirectional"))
    )
    (net (code "189") (name "unconnected-(U1-SD2-Pad17)") (class "Default")
      (node (ref "U1") (pin "17") (pinfunction "SD2_17") (pintype "bidirectional"))
    )
    (net (code "190") (name "unconnected-(U1-SD3-Pad18)") (class "Default")
      (node (ref "U1") (pin "18") (pinfunction "SD3_18") (pintype "bidirectional"))
    )
    (net (code "191") (name "unconnected-(U1-SVN-Pad5)") (class "Default")
      (node (ref "U1") (pin "5") (pinfunction "SVN_5") (pintype "bidirectional"))
    )
    (net (code "192") (name "unconnected-(U1-SVP-Pad4)") (class "Default")
      (node (ref "U1") (pin "4") (pinfunction "SVP_4") (pintype "bidirectional"))
    )
    (net (code "193") (name "unconnected-(U2A-PA02-Pad1)") (class "Default")
      (node (ref "U2") (pin "1") (pinfunction "PA02_1") (pintype "bidirectional"))
    )
    (net (code "194") (name "unconnected-(U2A-PA03-Pad2)") (class "Default")
      (node (ref "U2") (pin "2") (pinfunction "PA03_2") (pintype "bidirectional"))
    )
    (net (code "195") (name "unconnected-(U2A-PA04-Pad3)") (class "Default")
      (node (ref "U2") (pin "3") (pinfunction "PA04_3") (pintype "bidirectional"))
    )
    (net (code "196") (name "unconnected-(U2A-PA05-Pad4)") (class "Default")
      (node (ref "U2") (pin "4") (pinfunction "PA05_4") (pintype "bidirectional"))
    )
    (net (code "197") (name "unconnected-(U2A-PA06-Pad5)") (class "Default")
      (node (ref "U2") (pin "5") (pinfunction "PA06_5") (pintype "bidirectional"))
    )
    (net (code "198") (name "unconnected-(U2A-PA07-Pad6)") (class "Default")
      (node (ref "U2") (pin "6") (pinfunction "PA07_6") (pintype "bidirectional"))
    )
    (net (code "199") (name "unconnected-(U2A-PA08{slash}XIN32-Pad7)") (class "Default")
      (node (ref "U2") (pin "7") (pinfunction "PA08/XIN32_7") (pintype "bidirectional"))
    )
    (net (code "200") (name "unconnected-(U2A-PA09{slash}XOUT32-Pad8)") (class "Default")
      (node (ref "U2") (pin "8") (pinfunction "PA09/XOUT32_8") (pintype "bidirectional"))
    )
    (net (code "201") (name "unconnected-(U2A-PA10-Pad9)") (class "Default")
      (node (ref "U2") (pin "9") (pinfunction "PA10_9") (pintype "bidirectional"))
    )
    (net (code "202") (name "unconnected-(U2A-PA11-Pad10)") (class "Default")
      (node (ref "U2") (pin "10") (pinfunction "PA11_10") (pintype "bidirectional"))
    )
    (net (code "203") (name "unconnected-(U2A-PA16-Pad13)") (class "Default")
      (node (ref "U2") (pin "13") (pinfunction "PA16_13") (pintype "bidirectional"))
    )
    (net (code "204") (name "unconnected-(U2A-PA17-Pad14)") (class "Default")
      (node (ref "U2") (pin "14") (pinfunction "PA17_14") (pintype "bidirectional"))
    )
    (net (code "205") (name "unconnected-(U2A-PA27-Pad17)") (class "Default")
      (node (ref "U2") (pin "17") (pinfunction "PA27_17") (pintype "bidirectional"))
    )
    (net (code "206") (name "unconnected-(U6-1A-Pad3)") (class "Default")
      (node (ref "U6") (pin "3") (pinfunction "1A_3") (pintype "bidirectional"))
    )
    (net (code "207") (name "unconnected-(U6-1Y-Pad2)") (class "Default")
      (node (ref "U6") (pin "2") (pinfunction "1Y_2") (pintype "bidirectional"))
    )
    (net (code "208") (name "unconnected-(U6-4A-Pad9)") (class "Default")
      (node (ref "U6") (pin "9") (pinfunction "4A_9") (pintype "bidirectional"))
    )
    (net (code "209") (name "unconnected-(U6-4Y-Pad10)") (class "Default")
      (node (ref "U6") (pin "10") (pinfunction "4Y_10") (pintype "bidirectional"))
    )
    (net (code "210") (name "unconnected-(XTAL1-Pad1)") (class "Default")
      (node (ref "XTAL1") (pin "1") (pinfunction "1_1") (pintype "passive"))
    )
    (net (code "211") (name "unconnected-(XTAL1-Pad2)") (class "Default")
      (node (ref "XTAL1") (pin "2") (pinfunction "2_2") (pintype "passive"))
    )
  )
)
